# Arduino_Mega_DRAM_Tester_Shield.net
KiCad netlist of a schematic drawn in EAGLE
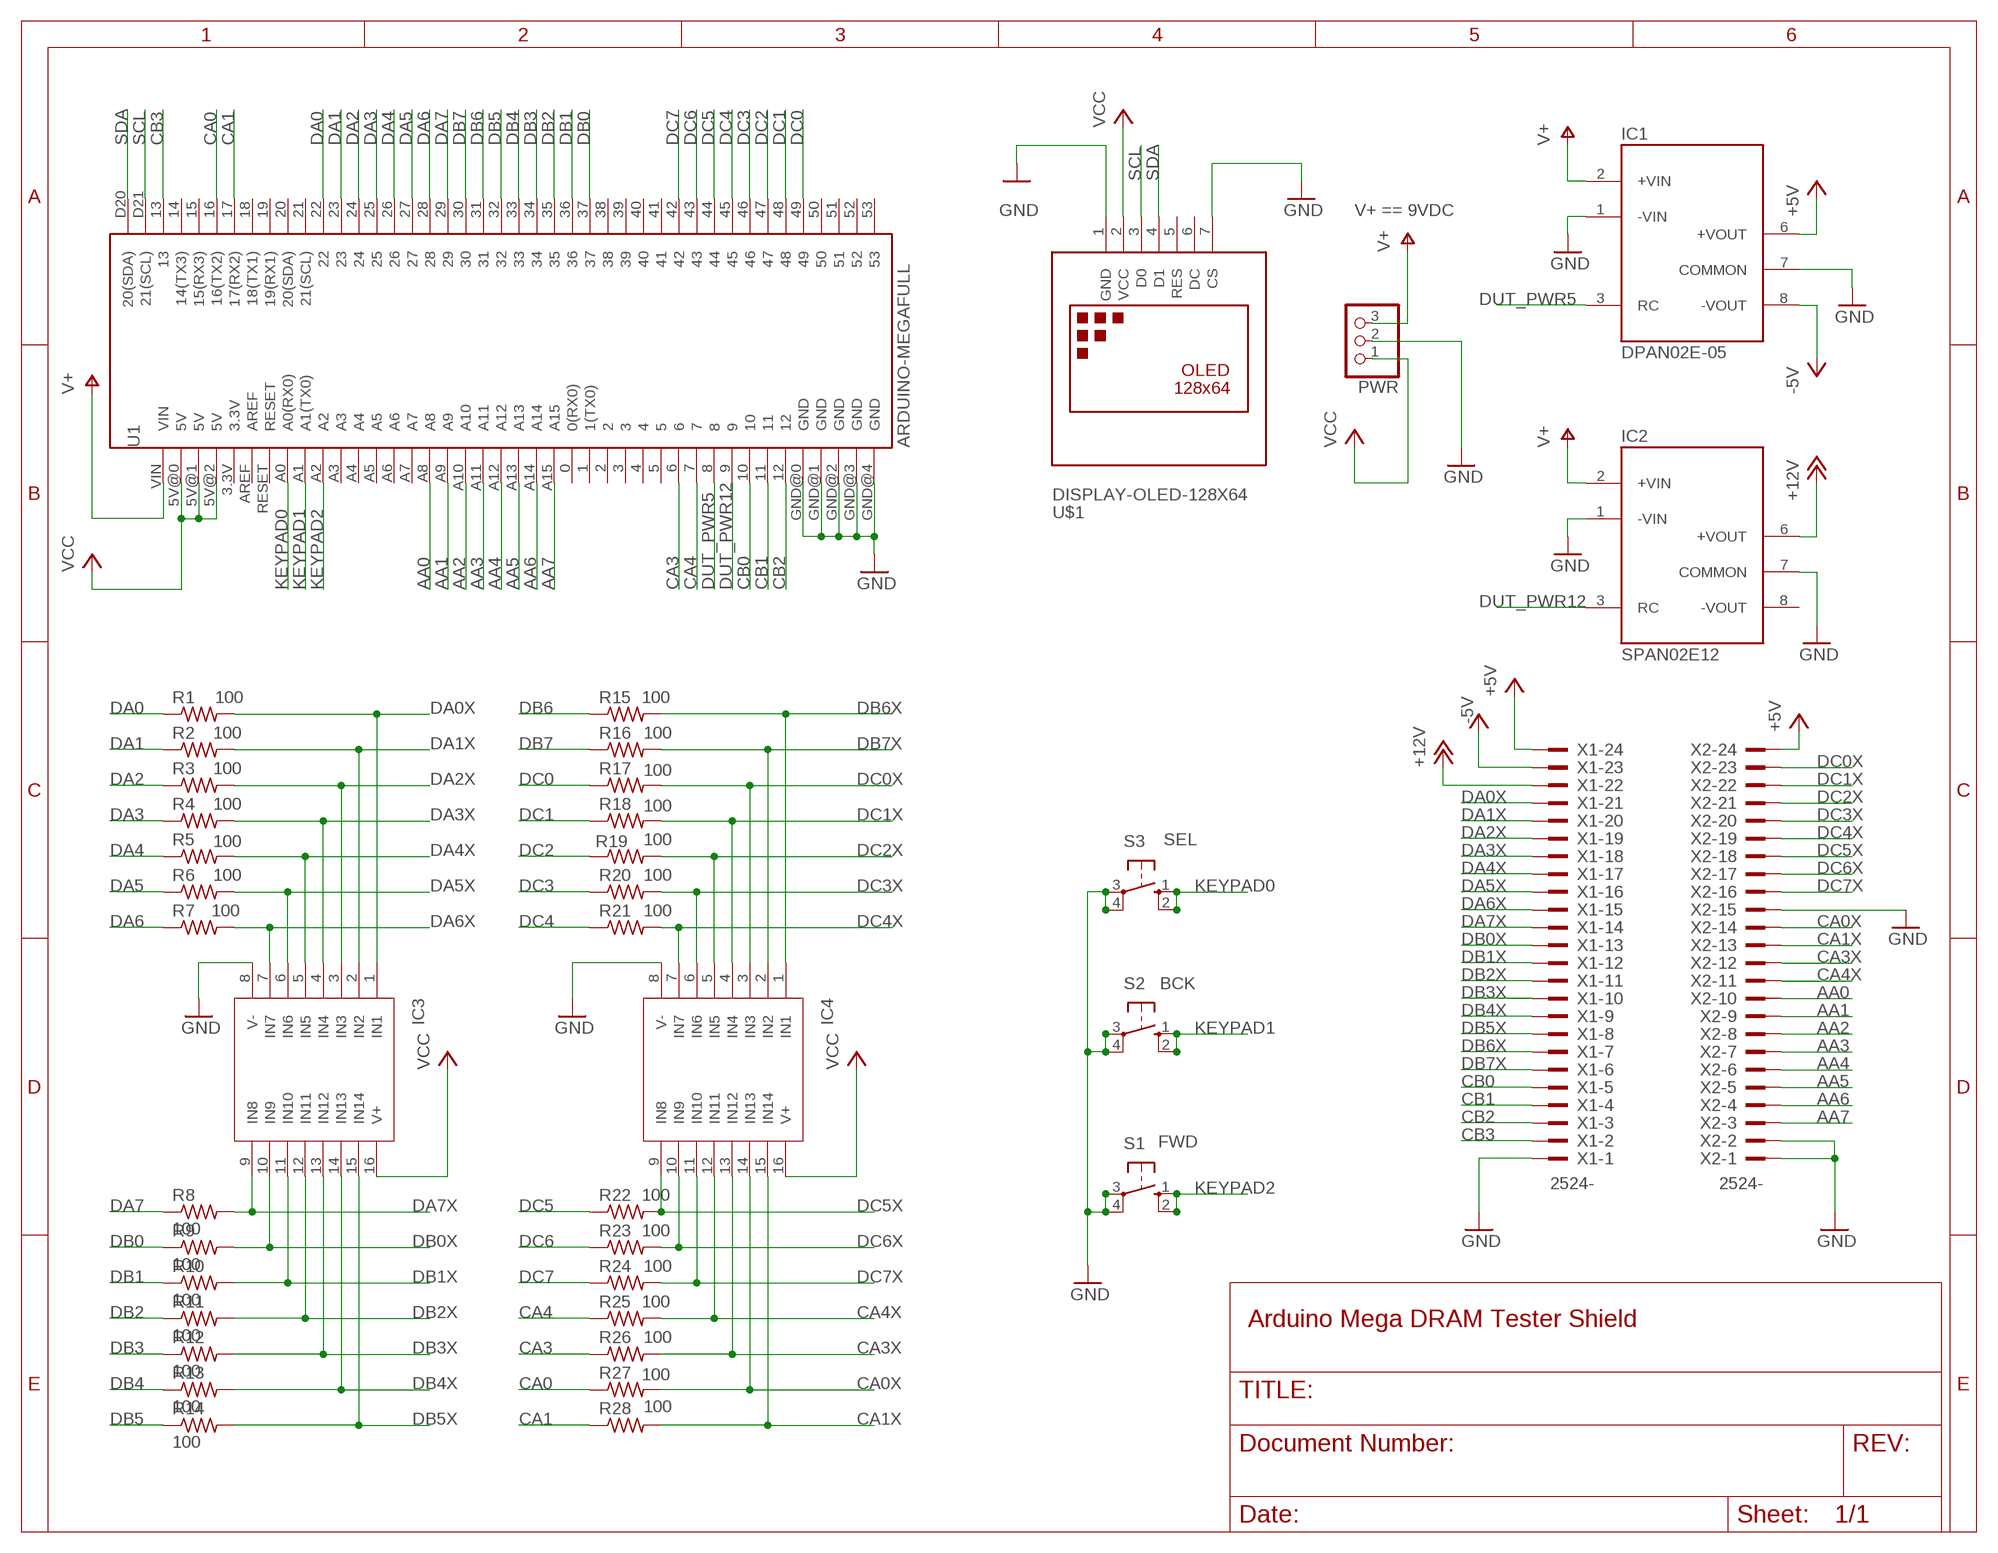
[diagram p0: schematic, sheet 1]

(export (version "E")
  (design (tool "Eeschema 10.0.6"))
  (components
    (comp (ref "IC1")
      (value "DPAN02E-05")
      (footprint "eagle-import:SIP7")
      (libsource (lib "eagle-import") (part "DPAN02"))
    )
    (comp (ref "IC2")
      (value "SPAN02E12")
      (footprint "eagle-import:SIP7")
      (libsource (lib "eagle-import") (part "DPAN02"))
    )
    (comp (ref "IC3")
      (value "SP720")
      (footprint "eagle-import:DIL16")
      (libsource (lib "eagle-import") (part "SP720"))
    )
    (comp (ref "IC4")
      (value "SP720")
      (footprint "eagle-import:DIL16")
      (libsource (lib "eagle-import") (part "SP720"))
    )
    (comp (ref "PWR")
      (value "PINHD-1X3")
      (footprint "eagle-import:1X03")
      (libsource (lib "eagle-import") (part "PINHD-1X3"))
    )
    (comp (ref "R1")
      (value "100")
      (footprint "eagle-import:0204_7")
      (libsource (lib "eagle-import") (part "R-US_0204/7"))
    )
    (comp (ref "R2")
      (value "100")
      (footprint "eagle-import:0204_7")
      (libsource (lib "eagle-import") (part "R-US_0204/7"))
    )
    (comp (ref "R3")
      (value "100")
      (footprint "eagle-import:0204_7")
      (libsource (lib "eagle-import") (part "R-US_0204/7"))
    )
    (comp (ref "R4")
      (value "100")
      (footprint "eagle-import:0204_7")
      (libsource (lib "eagle-import") (part "R-US_0204/7"))
    )
    (comp (ref "R5")
      (value "100")
      (footprint "eagle-import:0204_7")
      (libsource (lib "eagle-import") (part "R-US_0204/7"))
    )
    (comp (ref "R6")
      (value "100")
      (footprint "eagle-import:0204_7")
      (libsource (lib "eagle-import") (part "R-US_0204/7"))
    )
    (comp (ref "R7")
      (value "100")
      (footprint "eagle-import:0204_7")
      (libsource (lib "eagle-import") (part "R-US_0204/7"))
    )
    (comp (ref "R8")
      (value "100")
      (footprint "eagle-import:0204_7")
      (libsource (lib "eagle-import") (part "R-US_0204/7"))
    )
    (comp (ref "R9")
      (value "100")
      (footprint "eagle-import:0204_7")
      (libsource (lib "eagle-import") (part "R-US_0204/7"))
    )
    (comp (ref "R10")
      (value "100")
      (footprint "eagle-import:0204_7")
      (libsource (lib "eagle-import") (part "R-US_0204/7"))
    )
    (comp (ref "R11")
      (value "100")
      (footprint "eagle-import:0204_7")
      (libsource (lib "eagle-import") (part "R-US_0204/7"))
    )
    (comp (ref "R12")
      (value "100")
      (footprint "eagle-import:0204_7")
      (libsource (lib "eagle-import") (part "R-US_0204/7"))
    )
    (comp (ref "R13")
      (value "100")
      (footprint "eagle-import:0204_7")
      (libsource (lib "eagle-import") (part "R-US_0204/7"))
    )
    (comp (ref "R14")
      (value "100")
      (footprint "eagle-import:0204_7")
      (libsource (lib "eagle-import") (part "R-US_0204/7"))
    )
    (comp (ref "R15")
      (value "100")
      (footprint "eagle-import:0204_7")
      (libsource (lib "eagle-import") (part "R-US_0204/7"))
    )
    (comp (ref "R16")
      (value "100")
      (footprint "eagle-import:0204_7")
      (libsource (lib "eagle-import") (part "R-US_0204/7"))
    )
    (comp (ref "R17")
      (value "100")
      (footprint "eagle-import:0204_7")
      (libsource (lib "eagle-import") (part "R-US_0204/7"))
    )
    (comp (ref "R18")
      (value "100")
      (footprint "eagle-import:0204_7")
      (libsource (lib "eagle-import") (part "R-US_0204/7"))
    )
    (comp (ref "R19")
      (value "100")
      (footprint "eagle-import:0204_7")
      (libsource (lib "eagle-import") (part "R-US_0204/7"))
    )
    (comp (ref "R20")
      (value "100")
      (footprint "eagle-import:0204_7")
      (libsource (lib "eagle-import") (part "R-US_0204/7"))
    )
    (comp (ref "R21")
      (value "100")
      (footprint "eagle-import:0204_7")
      (libsource (lib "eagle-import") (part "R-US_0204/7"))
    )
    (comp (ref "R22")
      (value "100")
      (footprint "eagle-import:0204_7")
      (libsource (lib "eagle-import") (part "R-US_0204/7"))
    )
    (comp (ref "R23")
      (value "100")
      (footprint "eagle-import:0204_7")
      (libsource (lib "eagle-import") (part "R-US_0204/7"))
    )
    (comp (ref "R24")
      (value "100")
      (footprint "eagle-import:0204_7")
      (libsource (lib "eagle-import") (part "R-US_0204/7"))
    )
    (comp (ref "R25")
      (value "100")
      (footprint "eagle-import:0204_7")
      (libsource (lib "eagle-import") (part "R-US_0204/7"))
    )
    (comp (ref "R26")
      (value "100")
      (footprint "eagle-import:0204_7")
      (libsource (lib "eagle-import") (part "R-US_0204/7"))
    )
    (comp (ref "R27")
      (value "100")
      (footprint "eagle-import:0204_7")
      (libsource (lib "eagle-import") (part "R-US_0204/7"))
    )
    (comp (ref "R28")
      (value "100")
      (footprint "eagle-import:0204_7")
      (libsource (lib "eagle-import") (part "R-US_0204/7"))
    )
    (comp (ref "S1")
      (value "FWD")
      (footprint "eagle-import:B3F-10XX")
      (fields (field (name "MPN") "B3F-1000"))
      (libsource (lib "eagle-import") (part "10-XX"))
    )
    (comp (ref "S2")
      (value "BCK")
      (footprint "eagle-import:B3F-10XX")
      (fields (field (name "MPN") "B3F-1000"))
      (libsource (lib "eagle-import") (part "10-XX"))
    )
    (comp (ref "S3")
      (value "SEL")
      (footprint "eagle-import:B3F-10XX")
      (fields (field (name "MPN") "B3F-1000"))
      (libsource (lib "eagle-import") (part "10-XX"))
    )
    (comp (ref "U$1")
      (value "DISPLAY-OLED-128X64")
      (footprint "eagle-import:DISPLAY-OLED-128X64")
      (libsource (lib "eagle-import") (part "DISPLAY-OLED-128X64"))
    )
    (comp (ref "U1")
      (value "ARDUINO-MEGAFULL")
      (footprint "eagle-import:ARDUINO_MEGA")
      (libsource (lib "eagle-import") (part "ARDUINO-MEGAFULL"))
    )
    (comp (ref "X1")
      (value "2524-")
      (footprint "eagle-import:PAK100_2500-24")
      (libsource (lib "eagle-import") (part "2524-"))
    )
    (comp (ref "X2")
      (value "2524-")
      (footprint "eagle-import:PAK100_2500-24")
      (libsource (lib "eagle-import") (part "2524-"))
    )
  )
  (nets
    (net (code "1") (name "+5V") (class "Default")
      (node (ref "IC1") (pin "6") (pinfunction "+VOUT_6") (pintype "passive"))
      (node (ref "X1") (pin "24") (pinfunction "KL_24") (pintype "passive"))
      (node (ref "X2") (pin "24") (pinfunction "KL_24") (pintype "passive"))
    )
    (net (code "2") (name "+12V") (class "Default")
      (node (ref "IC2") (pin "6") (pinfunction "+VOUT_6") (pintype "passive"))
      (node (ref "X1") (pin "22") (pinfunction "KL_22") (pintype "passive"))
    )
    (net (code "3") (name "-5V") (class "Default")
      (node (ref "IC1") (pin "8") (pinfunction "-VOUT_8") (pintype "passive"))
      (node (ref "X1") (pin "23") (pinfunction "KL_23") (pintype "passive"))
    )
    (net (code "4") (name "/AA0") (class "Default")
      (node (ref "U1") (pin "A8") (pinfunction "A8_A8") (pintype "bidirectional"))
      (node (ref "X2") (pin "10") (pinfunction "KL_10") (pintype "passive"))
    )
    (net (code "5") (name "/AA1") (class "Default")
      (node (ref "U1") (pin "A9") (pinfunction "A9_A9") (pintype "bidirectional"))
      (node (ref "X2") (pin "9") (pinfunction "KL_9") (pintype "passive"))
    )
    (net (code "6") (name "/AA2") (class "Default")
      (node (ref "U1") (pin "A10") (pinfunction "A10_A10") (pintype "bidirectional"))
      (node (ref "X2") (pin "8") (pinfunction "KL_8") (pintype "passive"))
    )
    (net (code "7") (name "/AA3") (class "Default")
      (node (ref "U1") (pin "A11") (pinfunction "A11_A11") (pintype "bidirectional"))
      (node (ref "X2") (pin "7") (pinfunction "KL_7") (pintype "passive"))
    )
    (net (code "8") (name "/AA4") (class "Default")
      (node (ref "U1") (pin "A12") (pinfunction "A12_A12") (pintype "bidirectional"))
      (node (ref "X2") (pin "6") (pinfunction "KL_6") (pintype "passive"))
    )
    (net (code "9") (name "/AA5") (class "Default")
      (node (ref "U1") (pin "A13") (pinfunction "A13_A13") (pintype "bidirectional"))
      (node (ref "X2") (pin "5") (pinfunction "KL_5") (pintype "passive"))
    )
    (net (code "10") (name "/AA6") (class "Default")
      (node (ref "U1") (pin "A14") (pinfunction "A14_A14") (pintype "bidirectional"))
      (node (ref "X2") (pin "4") (pinfunction "KL_4") (pintype "passive"))
    )
    (net (code "11") (name "/AA7") (class "Default")
      (node (ref "U1") (pin "A15") (pinfunction "A15_A15") (pintype "bidirectional"))
      (node (ref "X2") (pin "3") (pinfunction "KL_3") (pintype "passive"))
    )
    (net (code "12") (name "/CA0") (class "Default")
      (node (ref "R27") (pin "1") (pinfunction "1_1") (pintype "passive"))
      (node (ref "U1") (pin "16") (pinfunction "16(TX2)_16") (pintype "bidirectional"))
    )
    (net (code "13") (name "/CA0X") (class "Default")
      (node (ref "IC4") (pin "14") (pinfunction "IN13_14") (pintype "input"))
      (node (ref "R27") (pin "2") (pinfunction "2_2") (pintype "passive"))
      (node (ref "X2") (pin "14") (pinfunction "KL_14") (pintype "passive"))
    )
    (net (code "14") (name "/CA1") (class "Default")
      (node (ref "R28") (pin "1") (pinfunction "1_1") (pintype "passive"))
      (node (ref "U1") (pin "17") (pinfunction "17(RX2)_17") (pintype "bidirectional"))
    )
    (net (code "15") (name "/CA1X") (class "Default")
      (node (ref "IC4") (pin "15") (pinfunction "IN14_15") (pintype "input"))
      (node (ref "R28") (pin "2") (pinfunction "2_2") (pintype "passive"))
      (node (ref "X2") (pin "13") (pinfunction "KL_13") (pintype "passive"))
    )
    (net (code "16") (name "/CA3") (class "Default")
      (node (ref "R26") (pin "1") (pinfunction "1_1") (pintype "passive"))
      (node (ref "U1") (pin "6") (pinfunction "6_6") (pintype "bidirectional"))
    )
    (net (code "17") (name "/CA3X") (class "Default")
      (node (ref "IC4") (pin "13") (pinfunction "IN12_13") (pintype "input"))
      (node (ref "R26") (pin "2") (pinfunction "2_2") (pintype "passive"))
      (node (ref "X2") (pin "12") (pinfunction "KL_12") (pintype "passive"))
    )
    (net (code "18") (name "/CA4") (class "Default")
      (node (ref "R25") (pin "1") (pinfunction "1_1") (pintype "passive"))
      (node (ref "U1") (pin "7") (pinfunction "7_7") (pintype "bidirectional"))
    )
    (net (code "19") (name "/CA4X") (class "Default")
      (node (ref "IC4") (pin "12") (pinfunction "IN11_12") (pintype "input"))
      (node (ref "R25") (pin "2") (pinfunction "2_2") (pintype "passive"))
      (node (ref "X2") (pin "11") (pinfunction "KL_11") (pintype "passive"))
    )
    (net (code "20") (name "/CB0") (class "Default")
      (node (ref "U1") (pin "10") (pinfunction "10_10") (pintype "bidirectional"))
      (node (ref "X1") (pin "5") (pinfunction "KL_5") (pintype "passive"))
    )
    (net (code "21") (name "/CB1") (class "Default")
      (node (ref "U1") (pin "11") (pinfunction "11_11") (pintype "bidirectional"))
      (node (ref "X1") (pin "4") (pinfunction "KL_4") (pintype "passive"))
    )
    (net (code "22") (name "/CB2") (class "Default")
      (node (ref "U1") (pin "12") (pinfunction "12_12") (pintype "bidirectional"))
      (node (ref "X1") (pin "3") (pinfunction "KL_3") (pintype "passive"))
    )
    (net (code "23") (name "/CB3") (class "Default")
      (node (ref "U1") (pin "13") (pinfunction "13_13") (pintype "bidirectional"))
      (node (ref "X1") (pin "2") (pinfunction "KL_2") (pintype "passive"))
    )
    (net (code "24") (name "/DA0") (class "Default")
      (node (ref "R1") (pin "1") (pinfunction "1_1") (pintype "passive"))
      (node (ref "U1") (pin "22") (pinfunction "22_22") (pintype "bidirectional"))
    )
    (net (code "25") (name "/DA0X") (class "Default")
      (node (ref "IC3") (pin "1") (pinfunction "IN1_1") (pintype "input"))
      (node (ref "R1") (pin "2") (pinfunction "2_2") (pintype "passive"))
      (node (ref "X1") (pin "21") (pinfunction "KL_21") (pintype "passive"))
    )
    (net (code "26") (name "/DA1") (class "Default")
      (node (ref "R2") (pin "1") (pinfunction "1_1") (pintype "passive"))
      (node (ref "U1") (pin "23") (pinfunction "23_23") (pintype "bidirectional"))
    )
    (net (code "27") (name "/DA1X") (class "Default")
      (node (ref "IC3") (pin "2") (pinfunction "IN2_2") (pintype "input"))
      (node (ref "R2") (pin "2") (pinfunction "2_2") (pintype "passive"))
      (node (ref "X1") (pin "20") (pinfunction "KL_20") (pintype "passive"))
    )
    (net (code "28") (name "/DA2") (class "Default")
      (node (ref "R3") (pin "1") (pinfunction "1_1") (pintype "passive"))
      (node (ref "U1") (pin "24") (pinfunction "24_24") (pintype "bidirectional"))
    )
    (net (code "29") (name "/DA2X") (class "Default")
      (node (ref "IC3") (pin "3") (pinfunction "IN3_3") (pintype "input"))
      (node (ref "R3") (pin "2") (pinfunction "2_2") (pintype "passive"))
      (node (ref "X1") (pin "19") (pinfunction "KL_19") (pintype "passive"))
    )
    (net (code "30") (name "/DA3") (class "Default")
      (node (ref "R4") (pin "1") (pinfunction "1_1") (pintype "passive"))
      (node (ref "U1") (pin "25") (pinfunction "25_25") (pintype "bidirectional"))
    )
    (net (code "31") (name "/DA3X") (class "Default")
      (node (ref "IC3") (pin "4") (pinfunction "IN4_4") (pintype "input"))
      (node (ref "R4") (pin "2") (pinfunction "2_2") (pintype "passive"))
      (node (ref "X1") (pin "18") (pinfunction "KL_18") (pintype "passive"))
    )
    (net (code "32") (name "/DA4") (class "Default")
      (node (ref "R5") (pin "1") (pinfunction "1_1") (pintype "passive"))
      (node (ref "U1") (pin "26") (pinfunction "26_26") (pintype "bidirectional"))
    )
    (net (code "33") (name "/DA4X") (class "Default")
      (node (ref "IC3") (pin "5") (pinfunction "IN5_5") (pintype "input"))
      (node (ref "R5") (pin "2") (pinfunction "2_2") (pintype "passive"))
      (node (ref "X1") (pin "17") (pinfunction "KL_17") (pintype "passive"))
    )
    (net (code "34") (name "/DA5") (class "Default")
      (node (ref "R6") (pin "1") (pinfunction "1_1") (pintype "passive"))
      (node (ref "U1") (pin "27") (pinfunction "27_27") (pintype "bidirectional"))
    )
    (net (code "35") (name "/DA5X") (class "Default")
      (node (ref "IC3") (pin "6") (pinfunction "IN6_6") (pintype "input"))
      (node (ref "R6") (pin "2") (pinfunction "2_2") (pintype "passive"))
      (node (ref "X1") (pin "16") (pinfunction "KL_16") (pintype "passive"))
    )
    (net (code "36") (name "/DA6") (class "Default")
      (node (ref "R7") (pin "1") (pinfunction "1_1") (pintype "passive"))
      (node (ref "U1") (pin "28") (pinfunction "28_28") (pintype "bidirectional"))
    )
    (net (code "37") (name "/DA6X") (class "Default")
      (node (ref "IC3") (pin "7") (pinfunction "IN7_7") (pintype "input"))
      (node (ref "R7") (pin "2") (pinfunction "2_2") (pintype "passive"))
      (node (ref "X1") (pin "15") (pinfunction "KL_15") (pintype "passive"))
    )
    (net (code "38") (name "/DA7") (class "Default")
      (node (ref "R8") (pin "1") (pinfunction "1_1") (pintype "passive"))
      (node (ref "U1") (pin "29") (pinfunction "29_29") (pintype "bidirectional"))
    )
    (net (code "39") (name "/DA7X") (class "Default")
      (node (ref "IC3") (pin "9") (pinfunction "IN8_9") (pintype "input"))
      (node (ref "R8") (pin "2") (pinfunction "2_2") (pintype "passive"))
      (node (ref "X1") (pin "14") (pinfunction "KL_14") (pintype "passive"))
    )
    (net (code "40") (name "/DB0") (class "Default")
      (node (ref "R9") (pin "1") (pinfunction "1_1") (pintype "passive"))
      (node (ref "U1") (pin "37") (pinfunction "37_37") (pintype "bidirectional"))
    )
    (net (code "41") (name "/DB0X") (class "Default")
      (node (ref "IC3") (pin "10") (pinfunction "IN9_10") (pintype "input"))
      (node (ref "R9") (pin "2") (pinfunction "2_2") (pintype "passive"))
      (node (ref "X1") (pin "13") (pinfunction "KL_13") (pintype "passive"))
    )
    (net (code "42") (name "/DB1") (class "Default")
      (node (ref "R10") (pin "1") (pinfunction "1_1") (pintype "passive"))
      (node (ref "U1") (pin "36") (pinfunction "36_36") (pintype "bidirectional"))
    )
    (net (code "43") (name "/DB1X") (class "Default")
      (node (ref "IC3") (pin "11") (pinfunction "IN10_11") (pintype "input"))
      (node (ref "R10") (pin "2") (pinfunction "2_2") (pintype "passive"))
      (node (ref "X1") (pin "12") (pinfunction "KL_12") (pintype "passive"))
    )
    (net (code "44") (name "/DB2") (class "Default")
      (node (ref "R11") (pin "1") (pinfunction "1_1") (pintype "passive"))
      (node (ref "U1") (pin "35") (pinfunction "35_35") (pintype "bidirectional"))
    )
    (net (code "45") (name "/DB2X") (class "Default")
      (node (ref "IC3") (pin "12") (pinfunction "IN11_12") (pintype "input"))
      (node (ref "R11") (pin "2") (pinfunction "2_2") (pintype "passive"))
      (node (ref "X1") (pin "11") (pinfunction "KL_11") (pintype "passive"))
    )
    (net (code "46") (name "/DB3") (class "Default")
      (node (ref "R12") (pin "1") (pinfunction "1_1") (pintype "passive"))
      (node (ref "U1") (pin "34") (pinfunction "34_34") (pintype "bidirectional"))
    )
    (net (code "47") (name "/DB3X") (class "Default")
      (node (ref "IC3") (pin "13") (pinfunction "IN12_13") (pintype "input"))
      (node (ref "R12") (pin "2") (pinfunction "2_2") (pintype "passive"))
      (node (ref "X1") (pin "10") (pinfunction "KL_10") (pintype "passive"))
    )
    (net (code "48") (name "/DB4") (class "Default")
      (node (ref "R13") (pin "1") (pinfunction "1_1") (pintype "passive"))
      (node (ref "U1") (pin "33") (pinfunction "33_33") (pintype "bidirectional"))
    )
    (net (code "49") (name "/DB4X") (class "Default")
      (node (ref "IC3") (pin "14") (pinfunction "IN13_14") (pintype "input"))
      (node (ref "R13") (pin "2") (pinfunction "2_2") (pintype "passive"))
      (node (ref "X1") (pin "9") (pinfunction "KL_9") (pintype "passive"))
    )
    (net (code "50") (name "/DB5") (class "Default")
      (node (ref "R14") (pin "1") (pinfunction "1_1") (pintype "passive"))
      (node (ref "U1") (pin "32") (pinfunction "32_32") (pintype "bidirectional"))
    )
    (net (code "51") (name "/DB5X") (class "Default")
      (node (ref "IC3") (pin "15") (pinfunction "IN14_15") (pintype "input"))
      (node (ref "R14") (pin "2") (pinfunction "2_2") (pintype "passive"))
      (node (ref "X1") (pin "8") (pinfunction "KL_8") (pintype "passive"))
    )
    (net (code "52") (name "/DB6") (class "Default")
      (node (ref "R15") (pin "1") (pinfunction "1_1") (pintype "passive"))
      (node (ref "U1") (pin "31") (pinfunction "31_31") (pintype "bidirectional"))
    )
    (net (code "53") (name "/DB6X") (class "Default")
      (node (ref "IC4") (pin "1") (pinfunction "IN1_1") (pintype "input"))
      (node (ref "R15") (pin "2") (pinfunction "2_2") (pintype "passive"))
      (node (ref "X1") (pin "7") (pinfunction "KL_7") (pintype "passive"))
    )
    (net (code "54") (name "/DB7") (class "Default")
      (node (ref "R16") (pin "1") (pinfunction "1_1") (pintype "passive"))
      (node (ref "U1") (pin "30") (pinfunction "30_30") (pintype "bidirectional"))
    )
    (net (code "55") (name "/DB7X") (class "Default")
      (node (ref "IC4") (pin "2") (pinfunction "IN2_2") (pintype "input"))
      (node (ref "R16") (pin "2") (pinfunction "2_2") (pintype "passive"))
      (node (ref "X1") (pin "6") (pinfunction "KL_6") (pintype "passive"))
    )
    (net (code "56") (name "/DC0") (class "Default")
      (node (ref "R17") (pin "1") (pinfunction "1_1") (pintype "passive"))
      (node (ref "U1") (pin "49") (pinfunction "49_49") (pintype "bidirectional"))
    )
    (net (code "57") (name "/DC0X") (class "Default")
      (node (ref "IC4") (pin "3") (pinfunction "IN3_3") (pintype "input"))
      (node (ref "R17") (pin "2") (pinfunction "2_2") (pintype "passive"))
      (node (ref "X2") (pin "23") (pinfunction "KL_23") (pintype "passive"))
    )
    (net (code "58") (name "/DC1") (class "Default")
      (node (ref "R18") (pin "1") (pinfunction "1_1") (pintype "passive"))
      (node (ref "U1") (pin "48") (pinfunction "48_48") (pintype "bidirectional"))
    )
    (net (code "59") (name "/DC1X") (class "Default")
      (node (ref "IC4") (pin "4") (pinfunction "IN4_4") (pintype "input"))
      (node (ref "R18") (pin "2") (pinfunction "2_2") (pintype "passive"))
      (node (ref "X2") (pin "22") (pinfunction "KL_22") (pintype "passive"))
    )
    (net (code "60") (name "/DC2") (class "Default")
      (node (ref "R19") (pin "1") (pinfunction "1_1") (pintype "passive"))
      (node (ref "U1") (pin "47") (pinfunction "47_47") (pintype "bidirectional"))
    )
    (net (code "61") (name "/DC2X") (class "Default")
      (node (ref "IC4") (pin "5") (pinfunction "IN5_5") (pintype "input"))
      (node (ref "R19") (pin "2") (pinfunction "2_2") (pintype "passive"))
      (node (ref "X2") (pin "21") (pinfunction "KL_21") (pintype "passive"))
    )
    (net (code "62") (name "/DC3") (class "Default")
      (node (ref "R20") (pin "1") (pinfunction "1_1") (pintype "passive"))
      (node (ref "U1") (pin "46") (pinfunction "46_46") (pintype "bidirectional"))
    )
    (net (code "63") (name "/DC3X") (class "Default")
      (node (ref "IC4") (pin "6") (pinfunction "IN6_6") (pintype "input"))
      (node (ref "R20") (pin "2") (pinfunction "2_2") (pintype "passive"))
      (node (ref "X2") (pin "20") (pinfunction "KL_20") (pintype "passive"))
    )
    (net (code "64") (name "/DC4") (class "Default")
      (node (ref "R21") (pin "1") (pinfunction "1_1") (pintype "passive"))
      (node (ref "U1") (pin "45") (pinfunction "45_45") (pintype "bidirectional"))
    )
    (net (code "65") (name "/DC4X") (class "Default")
      (node (ref "IC4") (pin "7") (pinfunction "IN7_7") (pintype "input"))
      (node (ref "R21") (pin "2") (pinfunction "2_2") (pintype "passive"))
      (node (ref "X2") (pin "19") (pinfunction "KL_19") (pintype "passive"))
    )
    (net (code "66") (name "/DC5") (class "Default")
      (node (ref "R22") (pin "1") (pinfunction "1_1") (pintype "passive"))
      (node (ref "U1") (pin "44") (pinfunction "44_44") (pintype "bidirectional"))
    )
    (net (code "67") (name "/DC5X") (class "Default")
      (node (ref "IC4") (pin "9") (pinfunction "IN8_9") (pintype "input"))
      (node (ref "R22") (pin "2") (pinfunction "2_2") (pintype "passive"))
      (node (ref "X2") (pin "18") (pinfunction "KL_18") (pintype "passive"))
    )
    (net (code "68") (name "/DC6") (class "Default")
      (node (ref "R23") (pin "1") (pinfunction "1_1") (pintype "passive"))
      (node (ref "U1") (pin "43") (pinfunction "43_43") (pintype "bidirectional"))
    )
    (net (code "69") (name "/DC6X") (class "Default")
      (node (ref "IC4") (pin "10") (pinfunction "IN9_10") (pintype "input"))
      (node (ref "R23") (pin "2") (pinfunction "2_2") (pintype "passive"))
      (node (ref "X2") (pin "17") (pinfunction "KL_17") (pintype "passive"))
    )
    (net (code "70") (name "/DC7") (class "Default")
      (node (ref "R24") (pin "1") (pinfunction "1_1") (pintype "passive"))
      (node (ref "U1") (pin "42") (pinfunction "42_42") (pintype "bidirectional"))
    )
    (net (code "71") (name "/DC7X") (class "Default")
      (node (ref "IC4") (pin "11") (pinfunction "IN10_11") (pintype "input"))
      (node (ref "R24") (pin "2") (pinfunction "2_2") (pintype "passive"))
      (node (ref "X2") (pin "16") (pinfunction "KL_16") (pintype "passive"))
    )
    (net (code "72") (name "/DUT_PWR5") (class "Default")
      (node (ref "IC1") (pin "3") (pinfunction "RC_3") (pintype "input"))
      (node (ref "U1") (pin "8") (pinfunction "8_8") (pintype "bidirectional"))
    )
    (net (code "73") (name "/DUT_PWR12") (class "Default")
      (node (ref "IC2") (pin "3") (pinfunction "RC_3") (pintype "input"))
      (node (ref "U1") (pin "9") (pinfunction "9_9") (pintype "bidirectional"))
    )
    (net (code "74") (name "/KEYPAD0") (class "Default")
      (node (ref "S3") (pin "1") (pinfunction "S_1") (pintype "passive"))
      (node (ref "S3") (pin "2") (pinfunction "S1_2") (pintype "passive"))
      (node (ref "U1") (pin "A0") (pinfunction "A0(RX0)_A0") (pintype "bidirectional"))
    )
    (net (code "75") (name "/KEYPAD1") (class "Default")
      (node (ref "S2") (pin "1") (pinfunction "S_1") (pintype "passive"))
      (node (ref "S2") (pin "2") (pinfunction "S1_2") (pintype "passive"))
      (node (ref "U1") (pin "A1") (pinfunction "A1(TX0)_A1") (pintype "bidirectional"))
    )
    (net (code "76") (name "/KEYPAD2") (class "Default")
      (node (ref "S1") (pin "1") (pinfunction "S_1") (pintype "passive"))
      (node (ref "S1") (pin "2") (pinfunction "S1_2") (pintype "passive"))
      (node (ref "U1") (pin "A2") (pinfunction "A2_A2") (pintype "bidirectional"))
    )
    (net (code "77") (name "/SCL") (class "Default")
      (node (ref "U$1") (pin "3") (pinfunction "D0_3") (pintype "bidirectional"))
      (node (ref "U1") (pin "D21") (pinfunction "21(SCL)_D21") (pintype "bidirectional"))
    )
    (net (code "78") (name "/SDA") (class "Default")
      (node (ref "U$1") (pin "4") (pinfunction "D1_4") (pintype "bidirectional"))
      (node (ref "U1") (pin "D20") (pinfunction "20(SDA)_D20") (pintype "bidirectional"))
    )
    (net (code "79") (name "GND") (class "Default")
      (node (ref "IC1") (pin "1") (pinfunction "-VIN_1") (pintype "input"))
      (node (ref "IC1") (pin "7") (pinfunction "COMMON_7") (pintype "passive"))
      (node (ref "IC2") (pin "1") (pinfunction "-VIN_1") (pintype "input"))
      (node (ref "IC2") (pin "7") (pinfunction "COMMON_7") (pintype "passive"))
      (node (ref "IC3") (pin "8") (pinfunction "V-_8") (pintype "input"))
      (node (ref "IC4") (pin "8") (pinfunction "V-_8") (pintype "input"))
      (node (ref "PWR") (pin "2") (pinfunction "2_2") (pintype "passive"))
      (node (ref "S1") (pin "3") (pinfunction "P_3") (pintype "passive"))
      (node (ref "S1") (pin "4") (pinfunction "P1_4") (pintype "passive"))
      (node (ref "S2") (pin "3") (pinfunction "P_3") (pintype "passive"))
      (node (ref "S2") (pin "4") (pinfunction "P1_4") (pintype "passive"))
      (node (ref "S3") (pin "3") (pinfunction "P_3") (pintype "passive"))
      (node (ref "S3") (pin "4") (pinfunction "P1_4") (pintype "passive"))
      (node (ref "U$1") (pin "1") (pinfunction "GND_1") (pintype "power_in"))
      (node (ref "U$1") (pin "7") (pinfunction "CS_7") (pintype "bidirectional"))
      (node (ref "U1") (pin "GND@0") (pinfunction "GND_GND@0") (pintype "bidirectional"))
      (node (ref "U1") (pin "GND@1") (pinfunction "GND_GND@1") (pintype "bidirectional"))
      (node (ref "U1") (pin "GND@2") (pinfunction "GND_GND@2") (pintype "bidirectional"))
      (node (ref "U1") (pin "GND@3") (pinfunction "GND_GND@3") (pintype "bidirectional"))
      (node (ref "U1") (pin "GND@4") (pinfunction "GND_GND@4") (pintype "bidirectional"))
      (node (ref "X1") (pin "1") (pinfunction "KL_1") (pintype "passive"))
      (node (ref "X2") (pin "1") (pinfunction "KL_1") (pintype "passive"))
      (node (ref "X2") (pin "15") (pinfunction "KL_15") (pintype "passive"))
      (node (ref "X2") (pin "2") (pinfunction "KL_2") (pintype "passive"))
    )
    (net (code "80") (name "V+") (class "Default")
      (node (ref "IC1") (pin "2") (pinfunction "+VIN_2") (pintype "input"))
      (node (ref "IC2") (pin "2") (pinfunction "+VIN_2") (pintype "input"))
      (node (ref "PWR") (pin "3") (pinfunction "3_3") (pintype "passive"))
      (node (ref "U1") (pin "VIN") (pinfunction "VIN_VIN") (pintype "bidirectional"))
    )
    (net (code "81") (name "VCC") (class "Default")
      (node (ref "IC3") (pin "16") (pinfunction "V+_16") (pintype "input"))
      (node (ref "IC4") (pin "16") (pinfunction "V+_16") (pintype "input"))
      (node (ref "PWR") (pin "1") (pinfunction "1_1") (pintype "passive"))
      (node (ref "U$1") (pin "2") (pinfunction "VCC_2") (pintype "power_in"))
      (node (ref "U1") (pin "5V@0") (pinfunction "5V_5V@0") (pintype "bidirectional"))
      (node (ref "U1") (pin "5V@1") (pinfunction "5V_5V@1") (pintype "bidirectional"))
      (node (ref "U1") (pin "5V@2") (pinfunction "5V_5V@2") (pintype "bidirectional"))
    )
    (net (code "82") (name "unconnected-(IC2--VOUT-Pad8)") (class "Default")
      (node (ref "IC2") (pin "8") (pinfunction "-VOUT_8") (pintype "passive"))
    )
    (net (code "83") (name "unconnected-(U$1-DC-Pad6)") (class "Default")
      (node (ref "U$1") (pin "6") (pinfunction "DC_6") (pintype "bidirectional"))
    )
    (net (code "84") (name "unconnected-(U$1-RES-Pad5)") (class "Default")
      (node (ref "U$1") (pin "5") (pinfunction "RES_5") (pintype "bidirectional"))
    )
    (net (code "85") (name "unconnected-(U1-0(RX0)-Pad0)") (class "Default")
      (node (ref "U1") (pin "0") (pinfunction "0(RX0)_0") (pintype "bidirectional"))
    )
    (net (code "86") (name "unconnected-(U1-1(TX0)-Pad1)") (class "Default")
      (node (ref "U1") (pin "1") (pinfunction "1(TX0)_1") (pintype "bidirectional"))
    )
    (net (code "87") (name "unconnected-(U1-14(TX3)-Pad14)") (class "Default")
      (node (ref "U1") (pin "14") (pinfunction "14(TX3)_14") (pintype "bidirectional"))
    )
    (net (code "88") (name "unconnected-(U1-15(RX3)-Pad15)") (class "Default")
      (node (ref "U1") (pin "15") (pinfunction "15(RX3)_15") (pintype "bidirectional"))
    )
    (net (code "89") (name "unconnected-(U1-18(TX1)-Pad18)") (class "Default")
      (node (ref "U1") (pin "18") (pinfunction "18(TX1)_18") (pintype "bidirectional"))
    )
    (net (code "90") (name "unconnected-(U1-19(RX1)-Pad19)") (class "Default")
      (node (ref "U1") (pin "19") (pinfunction "19(RX1)_19") (pintype "bidirectional"))
    )
    (net (code "91") (name "unconnected-(U1-20(SDA)-Pad20)") (class "Default")
      (node (ref "U1") (pin "20") (pinfunction "20(SDA)_20") (pintype "bidirectional"))
    )
    (net (code "92") (name "unconnected-(U1-21(SCL)-Pad21)") (class "Default")
      (node (ref "U1") (pin "21") (pinfunction "21(SCL)_21") (pintype "bidirectional"))
    )
    (net (code "93") (name "unconnected-(U1-Pad2)") (class "Default")
      (node (ref "U1") (pin "2") (pinfunction "2_2") (pintype "bidirectional"))
    )
    (net (code "94") (name "unconnected-(U1-Pad3)") (class "Default")
      (node (ref "U1") (pin "3") (pinfunction "3_3") (pintype "bidirectional"))
    )
    (net (code "95") (name "unconnected-(U1-Pad3.3V)") (class "Default")
      (node (ref "U1") (pin "3.3V") (pinfunction "3.3V_3.3V") (pintype "bidirectional"))
    )
    (net (code "96") (name "unconnected-(U1-Pad4)") (class "Default")
      (node (ref "U1") (pin "4") (pinfunction "4_4") (pintype "bidirectional"))
    )
    (net (code "97") (name "unconnected-(U1-Pad5)") (class "Default")
      (node (ref "U1") (pin "5") (pinfunction "5_5") (pintype "bidirectional"))
    )
    (net (code "98") (name "unconnected-(U1-Pad38)") (class "Default")
      (node (ref "U1") (pin "38") (pinfunction "38_38") (pintype "bidirectional"))
    )
    (net (code "99") (name "unconnected-(U1-Pad39)") (class "Default")
      (node (ref "U1") (pin "39") (pinfunction "39_39") (pintype "bidirectional"))
    )
    (net (code "100") (name "unconnected-(U1-Pad40)") (class "Default")
      (node (ref "U1") (pin "40") (pinfunction "40_40") (pintype "bidirectional"))
    )
    (net (code "101") (name "unconnected-(U1-Pad41)") (class "Default")
      (node (ref "U1") (pin "41") (pinfunction "41_41") (pintype "bidirectional"))
    )
    (net (code "102") (name "unconnected-(U1-Pad50)") (class "Default")
      (node (ref "U1") (pin "50") (pinfunction "50_50") (pintype "bidirectional"))
    )
    (net (code "103") (name "unconnected-(U1-Pad51)") (class "Default")
      (node (ref "U1") (pin "51") (pinfunction "51_51") (pintype "bidirectional"))
    )
    (net (code "104") (name "unconnected-(U1-Pad52)") (class "Default")
      (node (ref "U1") (pin "52") (pinfunction "52_52") (pintype "bidirectional"))
    )
    (net (code "105") (name "unconnected-(U1-Pad53)") (class "Default")
      (node (ref "U1") (pin "53") (pinfunction "53_53") (pintype "bidirectional"))
    )
    (net (code "106") (name "unconnected-(U1-PadA3)") (class "Default")
      (node (ref "U1") (pin "A3") (pinfunction "A3_A3") (pintype "bidirectional"))
    )
    (net (code "107") (name "unconnected-(U1-PadA4)") (class "Default")
      (node (ref "U1") (pin "A4") (pinfunction "A4_A4") (pintype "bidirectional"))
    )
    (net (code "108") (name "unconnected-(U1-PadA5)") (class "Default")
      (node (ref "U1") (pin "A5") (pinfunction "A5_A5") (pintype "bidirectional"))
    )
    (net (code "109") (name "unconnected-(U1-PadA6)") (class "Default")
      (node (ref "U1") (pin "A6") (pinfunction "A6_A6") (pintype "bidirectional"))
    )
    (net (code "110") (name "unconnected-(U1-PadA7)") (class "Default")
      (node (ref "U1") (pin "A7") (pinfunction "A7_A7") (pintype "bidirectional"))
    )
    (net (code "111") (name "unconnected-(U1-PadAREF)") (class "Default")
      (node (ref "U1") (pin "AREF") (pinfunction "AREF_AREF") (pintype "bidirectional"))
    )
    (net (code "112") (name "unconnected-(U1-PadRESET)") (class "Default")
      (node (ref "U1") (pin "RESET") (pinfunction "RESET_RESET") (pintype "bidirectional"))
    )
  )
)
